# RPM_TFT2.net
KiCad netlist of a schematic drawn in EAGLE
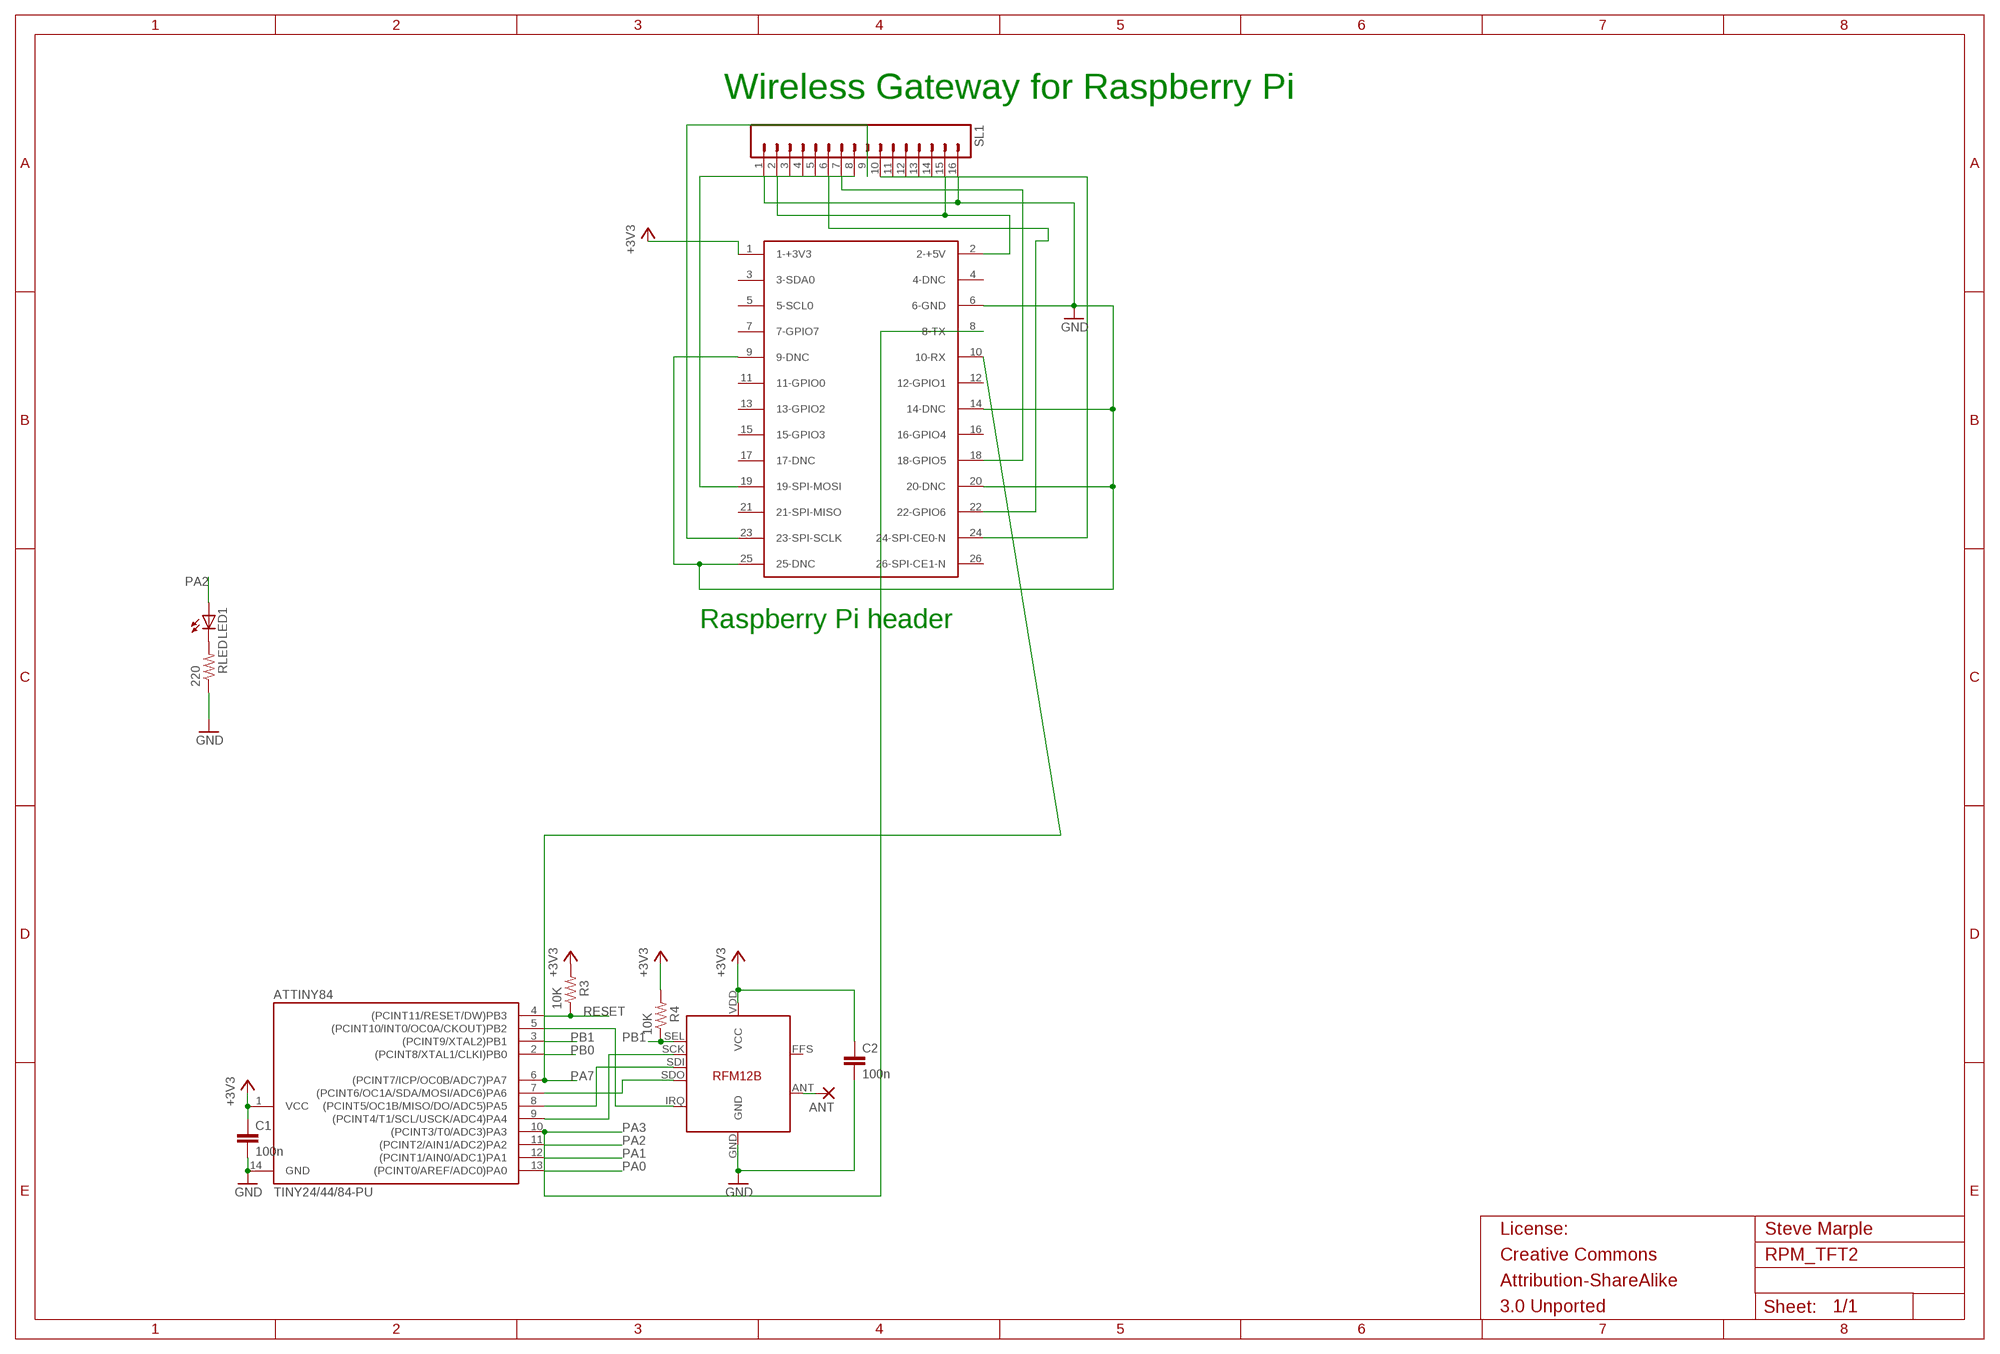
[diagram p0: schematic, sheet 1]

(export (version "E")
  (design (tool "Eeschema 10.0.6"))
  (components
    (comp (ref "ANT")
      (value "1,6/0,8")
      (footprint "eagle-import:1,6_0,8")
      (libsource (lib "eagle-import") (part "1,6/0,8"))
    )
    (comp (ref "ATTINY84")
      (value "TINY24/44/84-PU")
      (footprint "eagle-import:DIL14")
      (libsource (lib "eagle-import") (part "TINY24/44/84-PU"))
    )
    (comp (ref "C1")
      (value "100n")
      (footprint "eagle-import:C025-024X044")
      (libsource (lib "eagle-import") (part "C-EU025-024X044"))
    )
    (comp (ref "C2")
      (value "100n")
      (footprint "eagle-import:C025-024X044")
      (libsource (lib "eagle-import") (part "C-EU025-024X044"))
    )
    (comp (ref "LED1")
      (value "LED5MM")
      (footprint "eagle-import:LED5MM")
      (libsource (lib "eagle-import") (part "LED5MM"))
    )
    (comp (ref "R3")
      (value "10K")
      (footprint "eagle-import:AXIAL-0.3")
      (libsource (lib "eagle-import") (part "RESISTORAXIAL-0.3"))
    )
    (comp (ref "R4")
      (value "10K")
      (footprint "eagle-import:AXIAL-0.3")
      (libsource (lib "eagle-import") (part "RESISTORAXIAL-0.3"))
    )
    (comp (ref "RFM12B")
      (value "RFM12B")
      (footprint "eagle-import:RFM12B")
      (libsource (lib "eagle-import") (part "RFM12B"))
    )
    (comp (ref "RLED")
      (value "220")
      (footprint "eagle-import:AXIAL-0.3")
      (libsource (lib "eagle-import") (part "RESISTORAXIAL-0.3"))
    )
    (comp (ref "SL1")
      (value "M16")
      (footprint "eagle-import:16P")
      (libsource (lib "eagle-import") (part "M16"))
    )
    (comp (ref "X1")
      (value "P1A")
      (footprint "eagle-import:RASPBERRY-PI-HEADER")
      (libsource (lib "eagle-import") (part "RASPBERRY-PIHEADER"))
    )
  )
  (nets
    (net (code "1") (name "+3V3") (class "Default")
      (node (ref "ATTINY84") (pin "1") (pinfunction "VCC_1") (pintype "power_in"))
      (node (ref "C1") (pin "1") (pinfunction "1_1") (pintype "passive"))
      (node (ref "C2") (pin "1") (pinfunction "1_1") (pintype "passive"))
      (node (ref "R3") (pin "P$2") (pinfunction "2_P$2") (pintype "passive"))
      (node (ref "R4") (pin "P$2") (pinfunction "2_P$2") (pintype "passive"))
      (node (ref "RFM12B") (pin "VDD") (pinfunction "VCC_VDD") (pintype "power_in"))
      (node (ref "X1") (pin "1") (pinfunction "1-+3V3_1") (pintype "bidirectional"))
    )
    (net (code "2") (name "/PA0") (class "Default")
      (node (ref "ATTINY84") (pin "13") (pinfunction "(PCINT0/AREF/ADC0)PA0_13") (pintype "bidirectional"))
    )
    (net (code "3") (name "/PA1") (class "Default")
      (node (ref "ATTINY84") (pin "12") (pinfunction "(PCINT1/AIN0/ADC1)PA1_12") (pintype "bidirectional"))
    )
    (net (code "4") (name "/PA2") (class "Default")
      (node (ref "ATTINY84") (pin "11") (pinfunction "(PCINT2/AIN1/ADC2)PA2_11") (pintype "bidirectional"))
      (node (ref "LED1") (pin "A") (pinfunction "A_A") (pintype "passive"))
    )
    (net (code "5") (name "/PA3") (class "Default")
      (node (ref "ATTINY84") (pin "10") (pinfunction "(PCINT3/T0/ADC3)PA3_10") (pintype "bidirectional"))
      (node (ref "X1") (pin "8") (pinfunction "8-TX_8") (pintype "bidirectional"))
    )
    (net (code "6") (name "/PA7") (class "Default")
      (node (ref "ATTINY84") (pin "6") (pinfunction "(PCINT7/ICP/OC0B/ADC7)PA7_6") (pintype "bidirectional"))
      (node (ref "X1") (pin "10") (pinfunction "10-RX_10") (pintype "bidirectional"))
    )
    (net (code "7") (name "/PB0") (class "Default")
      (node (ref "ATTINY84") (pin "2") (pinfunction "(PCINT8/XTAL1/CLKI)PB0_2") (pintype "bidirectional"))
    )
    (net (code "8") (name "/PB1") (class "Default")
      (node (ref "ATTINY84") (pin "3") (pinfunction "(PCINT9/XTAL2)PB1_3") (pintype "bidirectional"))
      (node (ref "R4") (pin "P$1") (pinfunction "1_P$1") (pintype "passive"))
      (node (ref "RFM12B") (pin "SEL") (pinfunction "SEL_SEL") (pintype "input"))
    )
    (net (code "9") (name "/RESET") (class "Default")
      (node (ref "ATTINY84") (pin "4") (pinfunction "(PCINT11/RESET/DW)PB3_4") (pintype "bidirectional"))
      (node (ref "R3") (pin "P$1") (pinfunction "1_P$1") (pintype "passive"))
    )
    (net (code "10") (name "GND") (class "Default")
      (node (ref "ATTINY84") (pin "14") (pinfunction "GND_14") (pintype "power_in"))
      (node (ref "C1") (pin "2") (pinfunction "2_2") (pintype "passive"))
      (node (ref "C2") (pin "2") (pinfunction "2_2") (pintype "passive"))
      (node (ref "RFM12B") (pin "GND") (pinfunction "GND_GND") (pintype "power_in"))
      (node (ref "RLED") (pin "P$1") (pinfunction "1_P$1") (pintype "passive"))
      (node (ref "SL1") (pin "1") (pinfunction "1_1") (pintype "passive"))
      (node (ref "SL1") (pin "16") (pinfunction "16_16") (pintype "passive"))
      (node (ref "X1") (pin "14") (pinfunction "14-DNC_14") (pintype "bidirectional"))
      (node (ref "X1") (pin "20") (pinfunction "20-DNC_20") (pintype "bidirectional"))
      (node (ref "X1") (pin "25") (pinfunction "25-DNC_25") (pintype "bidirectional"))
      (node (ref "X1") (pin "6") (pinfunction "6-GND_6") (pintype "bidirectional"))
      (node (ref "X1") (pin "9") (pinfunction "9-DNC_9") (pintype "bidirectional"))
    )
    (net (code "11") (name "Net-(ANT-P)") (class "Default")
      (node (ref "ANT") (pin "1") (pinfunction "P_1") (pintype "passive"))
      (node (ref "RFM12B") (pin "ANT") (pinfunction "ANT_ANT") (pintype "passive"))
    )
    (net (code "12") (name "Net-(ATTINY84-(PCINT4{slash}T1{slash}SCL{slash}USCK{slash}ADC4)PA4)") (class "Default")
      (node (ref "ATTINY84") (pin "9") (pinfunction "(PCINT4/T1/SCL/USCK/ADC4)PA4_9") (pintype "bidirectional"))
      (node (ref "RFM12B") (pin "SCK") (pinfunction "SCK_SCK") (pintype "input"))
    )
    (net (code "13") (name "Net-(ATTINY84-(PCINT5{slash}OC1B{slash}MISO{slash}DO{slash}ADC5)PA5)") (class "Default")
      (node (ref "ATTINY84") (pin "8") (pinfunction "(PCINT5/OC1B/MISO/DO/ADC5)PA5_8") (pintype "bidirectional"))
      (node (ref "RFM12B") (pin "SDI") (pinfunction "SDI_SDI") (pintype "input"))
    )
    (net (code "14") (name "Net-(ATTINY84-(PCINT6{slash}OC1A{slash}SDA{slash}MOSI{slash}ADC6)PA6)") (class "Default")
      (node (ref "ATTINY84") (pin "7") (pinfunction "(PCINT6/OC1A/SDA/MOSI/ADC6)PA6_7") (pintype "bidirectional"))
      (node (ref "RFM12B") (pin "SDO") (pinfunction "SDO_SDO") (pintype "output"))
    )
    (net (code "15") (name "Net-(ATTINY84-(PCINT10{slash}INT0{slash}OC0A{slash}CKOUT)PB2)") (class "Default")
      (node (ref "ATTINY84") (pin "5") (pinfunction "(PCINT10/INT0/OC0A/CKOUT)PB2_5") (pintype "bidirectional"))
      (node (ref "RFM12B") (pin "IRQ") (pinfunction "IRQ_IRQ") (pintype "open_collector"))
    )
    (net (code "16") (name "Net-(LED1-C)") (class "Default")
      (node (ref "LED1") (pin "K") (pinfunction "C_K") (pintype "passive"))
      (node (ref "RLED") (pin "P$2") (pinfunction "2_P$2") (pintype "passive"))
    )
    (net (code "17") (name "Net-(X1-2-+5V)") (class "Default")
      (node (ref "SL1") (pin "15") (pinfunction "15_15") (pintype "passive"))
      (node (ref "SL1") (pin "2") (pinfunction "2_2") (pintype "passive"))
      (node (ref "X1") (pin "2") (pinfunction "2-+5V_2") (pintype "bidirectional"))
    )
    (net (code "18") (name "Net-(X1-18-GPIO5)") (class "Default")
      (node (ref "SL1") (pin "7") (pinfunction "7_7") (pintype "passive"))
      (node (ref "X1") (pin "18") (pinfunction "18-GPIO5_18") (pintype "bidirectional"))
    )
    (net (code "19") (name "Net-(X1-19-SPI-MOSI)") (class "Default")
      (node (ref "SL1") (pin "8") (pinfunction "8_8") (pintype "passive"))
      (node (ref "X1") (pin "19") (pinfunction "19-SPI-MOSI_19") (pintype "bidirectional"))
    )
    (net (code "20") (name "Net-(X1-22-GPIO6)") (class "Default")
      (node (ref "SL1") (pin "6") (pinfunction "6_6") (pintype "passive"))
      (node (ref "X1") (pin "22") (pinfunction "22-GPIO6_22") (pintype "bidirectional"))
    )
    (net (code "21") (name "Net-(X1-23-SPI-SCLK)") (class "Default")
      (node (ref "SL1") (pin "9") (pinfunction "9_9") (pintype "passive"))
      (node (ref "X1") (pin "23") (pinfunction "23-SPI-SCLK_23") (pintype "bidirectional"))
    )
    (net (code "22") (name "Net-(X1-24-SPI-CE0-N)") (class "Default")
      (node (ref "SL1") (pin "10") (pinfunction "10_10") (pintype "passive"))
      (node (ref "X1") (pin "24") (pinfunction "24-SPI-CE0-N_24") (pintype "bidirectional"))
    )
    (net (code "23") (name "unconnected-(RFM12B-PadFFS)") (class "Default")
      (node (ref "RFM12B") (pin "FFS") (pinfunction "FFS_FFS") (pintype "bidirectional"))
    )
    (net (code "24") (name "unconnected-(SL1-Pad3)") (class "Default")
      (node (ref "SL1") (pin "3") (pinfunction "3_3") (pintype "passive"))
    )
    (net (code "25") (name "unconnected-(SL1-Pad4)") (class "Default")
      (node (ref "SL1") (pin "4") (pinfunction "4_4") (pintype "passive"))
    )
    (net (code "26") (name "unconnected-(SL1-Pad5)") (class "Default")
      (node (ref "SL1") (pin "5") (pinfunction "5_5") (pintype "passive"))
    )
    (net (code "27") (name "unconnected-(SL1-Pad11)") (class "Default")
      (node (ref "SL1") (pin "11") (pinfunction "11_11") (pintype "passive"))
    )
    (net (code "28") (name "unconnected-(SL1-Pad12)") (class "Default")
      (node (ref "SL1") (pin "12") (pinfunction "12_12") (pintype "passive"))
    )
    (net (code "29") (name "unconnected-(SL1-Pad13)") (class "Default")
      (node (ref "SL1") (pin "13") (pinfunction "13_13") (pintype "passive"))
    )
    (net (code "30") (name "unconnected-(SL1-Pad14)") (class "Default")
      (node (ref "SL1") (pin "14") (pinfunction "14_14") (pintype "passive"))
    )
    (net (code "31") (name "unconnected-(X1-3-SDA0-Pad3)") (class "Default")
      (node (ref "X1") (pin "3") (pinfunction "3-SDA0_3") (pintype "bidirectional"))
    )
    (net (code "32") (name "unconnected-(X1-4-DNC-Pad4)") (class "Default")
      (node (ref "X1") (pin "4") (pinfunction "4-DNC_4") (pintype "bidirectional"))
    )
    (net (code "33") (name "unconnected-(X1-5-SCL0-Pad5)") (class "Default")
      (node (ref "X1") (pin "5") (pinfunction "5-SCL0_5") (pintype "bidirectional"))
    )
    (net (code "34") (name "unconnected-(X1-7-GPIO7-Pad7)") (class "Default")
      (node (ref "X1") (pin "7") (pinfunction "7-GPIO7_7") (pintype "bidirectional"))
    )
    (net (code "35") (name "unconnected-(X1-11-GPIO0-Pad11)") (class "Default")
      (node (ref "X1") (pin "11") (pinfunction "11-GPIO0_11") (pintype "bidirectional"))
    )
    (net (code "36") (name "unconnected-(X1-12-GPIO1-Pad12)") (class "Default")
      (node (ref "X1") (pin "12") (pinfunction "12-GPIO1_12") (pintype "bidirectional"))
    )
    (net (code "37") (name "unconnected-(X1-13-GPIO2-Pad13)") (class "Default")
      (node (ref "X1") (pin "13") (pinfunction "13-GPIO2_13") (pintype "bidirectional"))
    )
    (net (code "38") (name "unconnected-(X1-15-GPIO3-Pad15)") (class "Default")
      (node (ref "X1") (pin "15") (pinfunction "15-GPIO3_15") (pintype "bidirectional"))
    )
    (net (code "39") (name "unconnected-(X1-16-GPIO4-Pad16)") (class "Default")
      (node (ref "X1") (pin "16") (pinfunction "16-GPIO4_16") (pintype "bidirectional"))
    )
    (net (code "40") (name "unconnected-(X1-17-DNC-Pad17)") (class "Default")
      (node (ref "X1") (pin "17") (pinfunction "17-DNC_17") (pintype "bidirectional"))
    )
    (net (code "41") (name "unconnected-(X1-21-SPI-MISO-Pad21)") (class "Default")
      (node (ref "X1") (pin "21") (pinfunction "21-SPI-MISO_21") (pintype "bidirectional"))
    )
    (net (code "42") (name "unconnected-(X1-26-SPI-CE1-N-Pad26)") (class "Default")
      (node (ref "X1") (pin "26") (pinfunction "26-SPI-CE1-N_26") (pintype "bidirectional"))
    )
  )
)
